# r_wiring.net
KiCad netlist of a schematic drawn in EAGLE
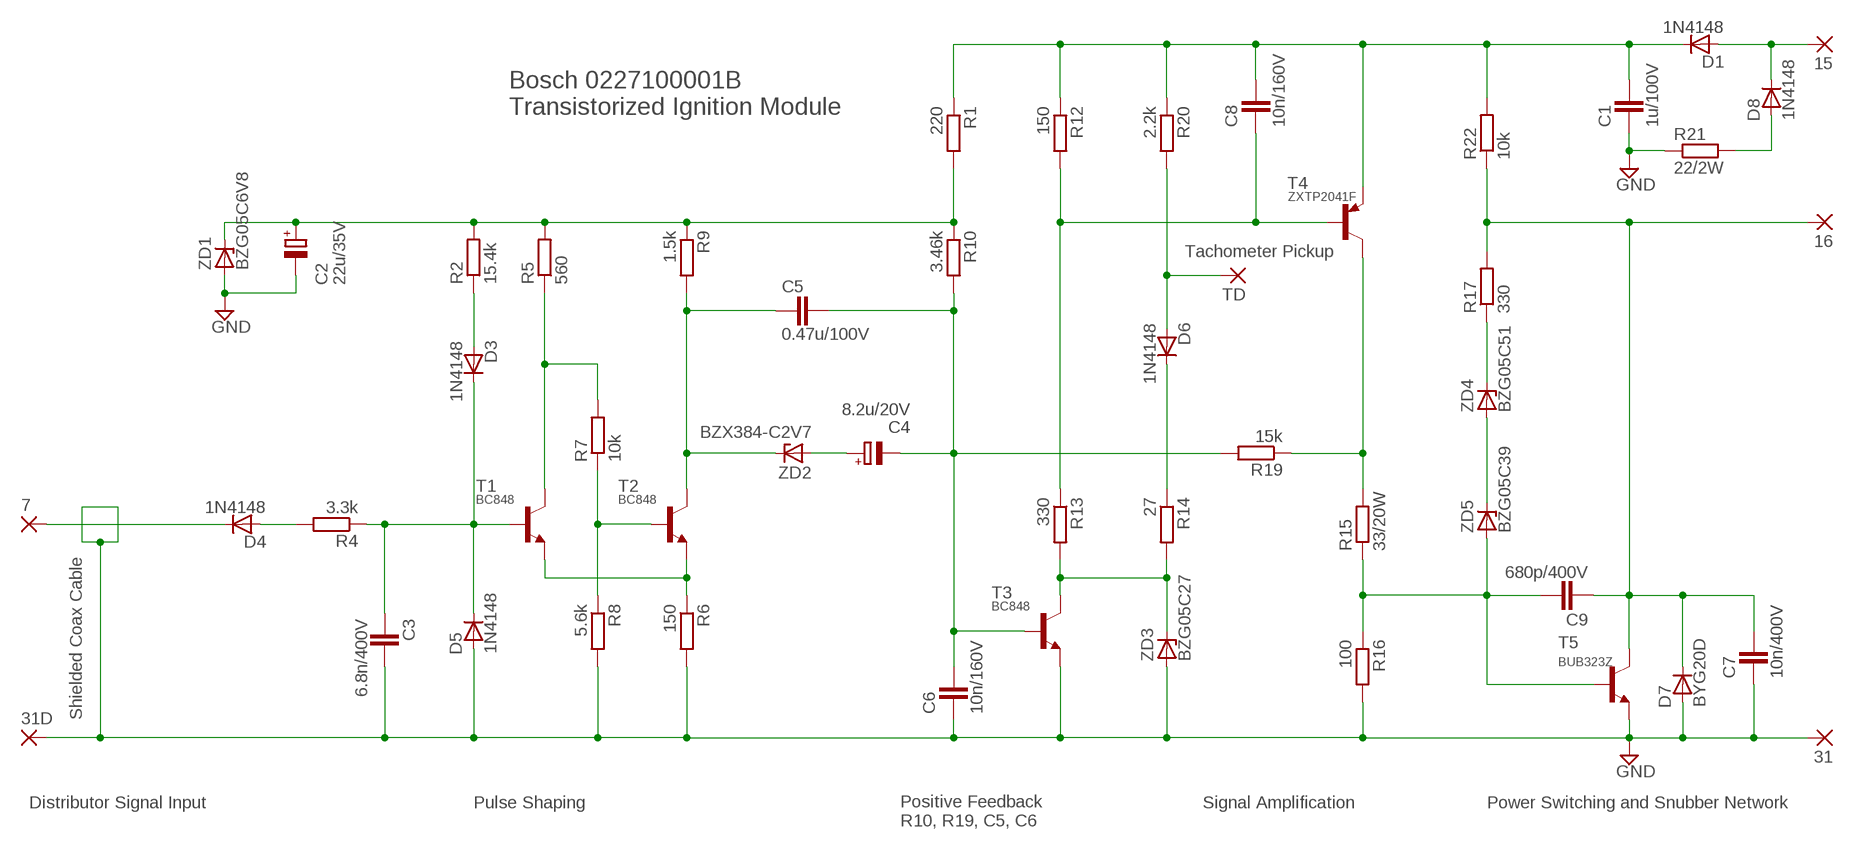
[diagram p0: schematic, sheet 1]

(export (version "E")
  (design (tool "Eeschema 10.0.6"))
  (components
    (comp (ref "7")
      (value "WIREPADSMD5-2,5")
      (footprint "eagle-import:5-2,5")
      (libsource (lib "eagle-import") (part "WIREPADSMD5-2,5"))
    )
    (comp (ref "15")
      (value "WIREPADSMD5-2,5")
      (footprint "eagle-import:5-2,5")
      (libsource (lib "eagle-import") (part "WIREPADSMD5-2,5"))
    )
    (comp (ref "16")
      (value "WIREPADSMD5-2,5")
      (footprint "eagle-import:5-2,5")
      (libsource (lib "eagle-import") (part "WIREPADSMD5-2,5"))
    )
    (comp (ref "31")
      (value "WIREPADSMD5-2,5")
      (footprint "eagle-import:5-2,5")
      (libsource (lib "eagle-import") (part "WIREPADSMD5-2,5"))
    )
    (comp (ref "31D")
      (value "WIREPADSMD5-2,5")
      (footprint "eagle-import:5-2,5")
      (libsource (lib "eagle-import") (part "WIREPADSMD5-2,5"))
    )
    (comp (ref "C1")
      (value "1u/100V")
      (footprint "eagle-import:C1206")
      (libsource (lib "eagle-import") (part "C-EUC1206"))
    )
    (comp (ref "C2")
      (value "22u/35V")
      (footprint "eagle-import:PANASONIC_G")
      (libsource (lib "eagle-import") (part "CPOL-EUG"))
    )
    (comp (ref "C3")
      (value "6.8n/400V")
      (footprint "eagle-import:C1206")
      (libsource (lib "eagle-import") (part "C-EUC1206"))
    )
    (comp (ref "C4")
      (value "8.2u/20V")
      (footprint "eagle-import:PANASONIC_G")
      (libsource (lib "eagle-import") (part "CPOL-EUG"))
    )
    (comp (ref "C5")
      (value "0.47u/100V")
      (footprint "eagle-import:C1206")
      (libsource (lib "eagle-import") (part "C-EUC1206"))
    )
    (comp (ref "C6")
      (value "10n/160V")
      (footprint "eagle-import:C1206")
      (libsource (lib "eagle-import") (part "C-EUC1206"))
    )
    (comp (ref "C7")
      (value "10n/400V")
      (footprint "eagle-import:C1206")
      (libsource (lib "eagle-import") (part "C-EUC1206"))
    )
    (comp (ref "C8")
      (value "10n/160V")
      (footprint "eagle-import:C1206")
      (libsource (lib "eagle-import") (part "C-EUC1206"))
    )
    (comp (ref "C9")
      (value "680p/400V")
      (footprint "eagle-import:C1206")
      (libsource (lib "eagle-import") (part "C-EUC1206"))
    )
    (comp (ref "D1")
      (value "1N4148")
      (footprint "eagle-import:SOD123")
      (libsource (lib "eagle-import") (part "DIODE-SOD123"))
    )
    (comp (ref "D3")
      (value "1N4148")
      (footprint "eagle-import:SOD123")
      (libsource (lib "eagle-import") (part "DIODE-SOD123"))
    )
    (comp (ref "D4")
      (value "1N4148")
      (footprint "eagle-import:SOD123")
      (libsource (lib "eagle-import") (part "DIODE-SOD123"))
    )
    (comp (ref "D5")
      (value "1N4148")
      (footprint "eagle-import:SOD123")
      (libsource (lib "eagle-import") (part "DIODE-SOD123"))
    )
    (comp (ref "D6")
      (value "1N4148")
      (footprint "eagle-import:SOD123")
      (libsource (lib "eagle-import") (part "DIODE-SOD123"))
    )
    (comp (ref "D7")
      (value "BYG20D")
      (footprint "eagle-import:DO214AC")
      (libsource (lib "eagle-import") (part "DIODE-DO214AC"))
    )
    (comp (ref "D8")
      (value "1N4148")
      (footprint "eagle-import:SOD123")
      (libsource (lib "eagle-import") (part "DIODE-SOD123"))
    )
    (comp (ref "R1")
      (value "220")
      (footprint "eagle-import:R2512")
      (libsource (lib "eagle-import") (part "resistor_R-EU_R2512"))
    )
    (comp (ref "R2")
      (value "15.4k")
      (footprint "eagle-import:R2512")
      (libsource (lib "eagle-import") (part "resistor_R-EU_R2512"))
    )
    (comp (ref "R4")
      (value "3.3k")
      (footprint "eagle-import:R2512")
      (libsource (lib "eagle-import") (part "resistor_R-EU_R2512"))
    )
    (comp (ref "R5")
      (value "560")
      (footprint "eagle-import:R2512")
      (libsource (lib "eagle-import") (part "resistor_R-EU_R2512"))
    )
    (comp (ref "R6")
      (value "150")
      (footprint "eagle-import:R2512")
      (libsource (lib "eagle-import") (part "resistor_R-EU_R2512"))
    )
    (comp (ref "R7")
      (value "10k")
      (footprint "eagle-import:R2512")
      (libsource (lib "eagle-import") (part "resistor_R-EU_R2512"))
    )
    (comp (ref "R8")
      (value "5.6k")
      (footprint "eagle-import:R2512")
      (libsource (lib "eagle-import") (part "resistor_R-EU_R2512"))
    )
    (comp (ref "R9")
      (value "1.5k")
      (footprint "eagle-import:R2512")
      (libsource (lib "eagle-import") (part "resistor_R-EU_R2512"))
    )
    (comp (ref "R10")
      (value "3.46k")
      (footprint "eagle-import:R2512")
      (libsource (lib "eagle-import") (part "resistor_R-EU_R2512"))
    )
    (comp (ref "R12")
      (value "150")
      (footprint "eagle-import:R2512")
      (libsource (lib "eagle-import") (part "resistor_R-EU_R2512"))
    )
    (comp (ref "R13")
      (value "330")
      (footprint "eagle-import:R2512")
      (libsource (lib "eagle-import") (part "resistor_R-EU_R2512"))
    )
    (comp (ref "R14")
      (value "27")
      (footprint "eagle-import:R2512")
      (libsource (lib "eagle-import") (part "resistor_R-EU_R2512"))
    )
    (comp (ref "R15")
      (value "33/20W")
      (footprint "eagle-import:DPAK")
      (libsource (lib "eagle-import") (part "R-EU_DPAK"))
    )
    (comp (ref "R16")
      (value "100")
      (footprint "eagle-import:R2512")
      (libsource (lib "eagle-import") (part "R-EU_R2512"))
    )
    (comp (ref "R17")
      (value "330")
      (footprint "eagle-import:R2512")
      (libsource (lib "eagle-import") (part "resistor_R-EU_R2512"))
    )
    (comp (ref "R19")
      (value "15k")
      (footprint "eagle-import:R2512")
      (libsource (lib "eagle-import") (part "R-EU_R2512"))
    )
    (comp (ref "R20")
      (value "2.2k")
      (footprint "eagle-import:R2512")
      (libsource (lib "eagle-import") (part "resistor_R-EU_R2512"))
    )
    (comp (ref "R21")
      (value "22/2W")
      (footprint "eagle-import:R2512")
      (libsource (lib "eagle-import") (part "resistor_R-EU_R2512"))
    )
    (comp (ref "R22")
      (value "10k")
      (footprint "eagle-import:R2512")
      (libsource (lib "eagle-import") (part "R-EU_R2512"))
    )
    (comp (ref "T1")
      (value "BC848")
      (footprint "eagle-import:SOT23")
      (libsource (lib "eagle-import") (part "BC848"))
    )
    (comp (ref "T2")
      (value "BC848")
      (footprint "eagle-import:SOT23")
      (libsource (lib "eagle-import") (part "BC848"))
    )
    (comp (ref "T3")
      (value "BC848")
      (footprint "eagle-import:SOT23")
      (libsource (lib "eagle-import") (part "BC848"))
    )
    (comp (ref "T4")
      (value "ZXTP2041F")
      (footprint "eagle-import:SOT23-BCE")
      (libsource (lib "eagle-import") (part "-PNP-SOT23-BCE"))
    )
    (comp (ref "T5")
      (value "BUB323Z")
      (footprint "eagle-import:DPAK")
      (libsource (lib "eagle-import") (part "-NPN-DPAK-BEC"))
    )
    (comp (ref "TD")
      (value "WIREPADSMD5-2,5")
      (footprint "eagle-import:5-2,5")
      (libsource (lib "eagle-import") (part "WIREPADSMD5-2,5"))
    )
    (comp (ref "ZD1")
      (value "BZG05C6V8")
      (footprint "eagle-import:SMB")
      (libsource (lib "eagle-import") (part "ZENER-DIODESMB"))
    )
    (comp (ref "ZD2")
      (value "BZX384-C2V7")
      (footprint "eagle-import:SOD-323F")
      (libsource (lib "eagle-import") (part "ZENERSOD-323F"))
    )
    (comp (ref "ZD3")
      (value "BZG05C27")
      (footprint "eagle-import:SMB")
      (libsource (lib "eagle-import") (part "ZENER-DIODESMB"))
    )
    (comp (ref "ZD4")
      (value "BZG05C51")
      (footprint "eagle-import:SMB")
      (libsource (lib "eagle-import") (part "ZENER-DIODESMB"))
    )
    (comp (ref "ZD5")
      (value "BZG05C39")
      (footprint "eagle-import:SMB")
      (libsource (lib "eagle-import") (part "ZENER-DIODESMB"))
    )
  )
  (nets
    (net (code "1") (name "GND") (class "Default")
      (node (ref "31") (pin "1") (pinfunction "P_1") (pintype "passive"))
      (node (ref "31D") (pin "1") (pinfunction "P_1") (pintype "passive"))
      (node (ref "C1") (pin "2") (pinfunction "2_2") (pintype "passive"))
      (node (ref "C2") (pin "-") (pinfunction "-_-") (pintype "passive"))
      (node (ref "C3") (pin "1") (pinfunction "1_1") (pintype "passive"))
      (node (ref "C6") (pin "2") (pinfunction "2_2") (pintype "passive"))
      (node (ref "C7") (pin "2") (pinfunction "2_2") (pintype "passive"))
      (node (ref "D5") (pin "A") (pinfunction "A_A") (pintype "passive"))
      (node (ref "D7") (pin "A") (pinfunction "A_A") (pintype "passive"))
      (node (ref "R16") (pin "2") (pinfunction "2_2") (pintype "passive"))
      (node (ref "R21") (pin "1") (pinfunction "1_1") (pintype "passive"))
      (node (ref "R6") (pin "2") (pinfunction "2_2") (pintype "passive"))
      (node (ref "R8") (pin "2") (pinfunction "2_2") (pintype "passive"))
      (node (ref "T3") (pin "2") (pinfunction "E_2") (pintype "passive"))
      (node (ref "T5") (pin "3") (pinfunction "E_3") (pintype "passive"))
      (node (ref "ZD1") (pin "A") (pinfunction "A_A") (pintype "passive"))
      (node (ref "ZD3") (pin "A") (pinfunction "A_A") (pintype "passive"))
    )
    (net (code "2") (name "Net-(7-P)") (class "Default")
      (node (ref "7") (pin "1") (pinfunction "P_1") (pintype "passive"))
      (node (ref "D4") (pin "C") (pinfunction "C_C") (pintype "passive"))
    )
    (net (code "3") (name "Net-(15-P)") (class "Default")
      (node (ref "15") (pin "1") (pinfunction "P_1") (pintype "passive"))
      (node (ref "D1") (pin "A") (pinfunction "A_A") (pintype "passive"))
      (node (ref "D8") (pin "C") (pinfunction "C_C") (pintype "passive"))
    )
    (net (code "4") (name "Net-(16-P)") (class "Default")
      (node (ref "16") (pin "1") (pinfunction "P_1") (pintype "passive"))
      (node (ref "C7") (pin "1") (pinfunction "1_1") (pintype "passive"))
      (node (ref "C9") (pin "2") (pinfunction "2_2") (pintype "passive"))
      (node (ref "D7") (pin "C") (pinfunction "C_C") (pintype "passive"))
      (node (ref "R17") (pin "2") (pinfunction "2_2") (pintype "passive"))
      (node (ref "R22") (pin "1") (pinfunction "1_1") (pintype "passive"))
      (node (ref "T5") (pin "4") (pinfunction "C_4") (pintype "passive"))
    )
    (net (code "5") (name "Net-(C1-Pad1)") (class "Default")
      (node (ref "C1") (pin "1") (pinfunction "1_1") (pintype "passive"))
      (node (ref "C8") (pin "1") (pinfunction "1_1") (pintype "passive"))
      (node (ref "D1") (pin "C") (pinfunction "C_C") (pintype "passive"))
      (node (ref "R1") (pin "1") (pinfunction "1_1") (pintype "passive"))
      (node (ref "R12") (pin "1") (pinfunction "1_1") (pintype "passive"))
      (node (ref "R20") (pin "1") (pinfunction "1_1") (pintype "passive"))
      (node (ref "R22") (pin "2") (pinfunction "2_2") (pintype "passive"))
      (node (ref "T4") (pin "E") (pinfunction "E_E") (pintype "passive"))
    )
    (net (code "6") (name "Net-(C2-Pad+)") (class "Default")
      (node (ref "C2") (pin "+") (pinfunction "+_+") (pintype "passive"))
      (node (ref "R1") (pin "2") (pinfunction "2_2") (pintype "passive"))
      (node (ref "R10") (pin "1") (pinfunction "1_1") (pintype "passive"))
      (node (ref "R2") (pin "2") (pinfunction "2_2") (pintype "passive"))
      (node (ref "R5") (pin "2") (pinfunction "2_2") (pintype "passive"))
      (node (ref "R9") (pin "1") (pinfunction "1_1") (pintype "passive"))
      (node (ref "ZD1") (pin "C") (pinfunction "C_C") (pintype "passive"))
    )
    (net (code "7") (name "Net-(C4-Pad+)") (class "Default")
      (node (ref "C4") (pin "+") (pinfunction "+_+") (pintype "passive"))
      (node (ref "ZD2") (pin "A") (pinfunction "A_A") (pintype "passive"))
    )
    (net (code "8") (name "Net-(C8-Pad2)") (class "Default")
      (node (ref "C8") (pin "2") (pinfunction "2_2") (pintype "passive"))
      (node (ref "R12") (pin "2") (pinfunction "2_2") (pintype "passive"))
      (node (ref "R13") (pin "1") (pinfunction "1_1") (pintype "passive"))
      (node (ref "T4") (pin "B") (pinfunction "B_B") (pintype "passive"))
    )
    (net (code "9") (name "Net-(D3-PadA)") (class "Default")
      (node (ref "D3") (pin "A") (pinfunction "A_A") (pintype "passive"))
      (node (ref "R2") (pin "1") (pinfunction "1_1") (pintype "passive"))
    )
    (net (code "10") (name "Net-(D4-PadA)") (class "Default")
      (node (ref "D4") (pin "A") (pinfunction "A_A") (pintype "passive"))
      (node (ref "R4") (pin "2") (pinfunction "2_2") (pintype "passive"))
    )
    (net (code "11") (name "Net-(D6-PadC)") (class "Default")
      (node (ref "D6") (pin "C") (pinfunction "C_C") (pintype "passive"))
      (node (ref "R14") (pin "1") (pinfunction "1_1") (pintype "passive"))
    )
    (net (code "12") (name "Net-(D8-PadA)") (class "Default")
      (node (ref "D8") (pin "A") (pinfunction "A_A") (pintype "passive"))
      (node (ref "R21") (pin "2") (pinfunction "2_2") (pintype "passive"))
    )
    (net (code "13") (name "Net-(R15-2)") (class "Default")
      (node (ref "R15") (pin "3") (pinfunction "2_3") (pintype "passive"))
      (node (ref "R19") (pin "1") (pinfunction "1_1") (pintype "passive"))
      (node (ref "T4") (pin "C") (pinfunction "C_C") (pintype "passive"))
    )
    (net (code "14") (name "Net-(R17-Pad1)") (class "Default")
      (node (ref "R17") (pin "1") (pinfunction "1_1") (pintype "passive"))
      (node (ref "ZD4") (pin "C") (pinfunction "C_C") (pintype "passive"))
    )
    (net (code "15") (name "Net-(T1-B)") (class "Default")
      (node (ref "C3") (pin "2") (pinfunction "2_2") (pintype "passive"))
      (node (ref "D3") (pin "C") (pinfunction "C_C") (pintype "passive"))
      (node (ref "D5") (pin "C") (pinfunction "C_C") (pintype "passive"))
      (node (ref "R4") (pin "1") (pinfunction "1_1") (pintype "passive"))
      (node (ref "T1") (pin "1") (pinfunction "B_1") (pintype "passive"))
    )
    (net (code "16") (name "Net-(T1-C)") (class "Default")
      (node (ref "R5") (pin "1") (pinfunction "1_1") (pintype "passive"))
      (node (ref "R7") (pin "2") (pinfunction "2_2") (pintype "passive"))
      (node (ref "T1") (pin "3") (pinfunction "C_3") (pintype "passive"))
    )
    (net (code "17") (name "Net-(T1-E)") (class "Default")
      (node (ref "R6") (pin "1") (pinfunction "1_1") (pintype "passive"))
      (node (ref "T1") (pin "2") (pinfunction "E_2") (pintype "passive"))
      (node (ref "T2") (pin "2") (pinfunction "E_2") (pintype "passive"))
    )
    (net (code "18") (name "Net-(T2-B)") (class "Default")
      (node (ref "R7") (pin "1") (pinfunction "1_1") (pintype "passive"))
      (node (ref "R8") (pin "1") (pinfunction "1_1") (pintype "passive"))
      (node (ref "T2") (pin "1") (pinfunction "B_1") (pintype "passive"))
    )
    (net (code "19") (name "Net-(T2-C)") (class "Default")
      (node (ref "C5") (pin "2") (pinfunction "2_2") (pintype "passive"))
      (node (ref "R9") (pin "2") (pinfunction "2_2") (pintype "passive"))
      (node (ref "T2") (pin "3") (pinfunction "C_3") (pintype "passive"))
      (node (ref "ZD2") (pin "C") (pinfunction "C_C") (pintype "passive"))
    )
    (net (code "20") (name "Net-(T3-B)") (class "Default")
      (node (ref "C4") (pin "-") (pinfunction "-_-") (pintype "passive"))
      (node (ref "C5") (pin "1") (pinfunction "1_1") (pintype "passive"))
      (node (ref "C6") (pin "1") (pinfunction "1_1") (pintype "passive"))
      (node (ref "R10") (pin "2") (pinfunction "2_2") (pintype "passive"))
      (node (ref "R19") (pin "2") (pinfunction "2_2") (pintype "passive"))
      (node (ref "T3") (pin "1") (pinfunction "B_1") (pintype "passive"))
    )
    (net (code "21") (name "Net-(T3-C)") (class "Default")
      (node (ref "R13") (pin "2") (pinfunction "2_2") (pintype "passive"))
      (node (ref "R14") (pin "2") (pinfunction "2_2") (pintype "passive"))
      (node (ref "T3") (pin "3") (pinfunction "C_3") (pintype "passive"))
      (node (ref "ZD3") (pin "C") (pinfunction "C_C") (pintype "passive"))
    )
    (net (code "22") (name "Net-(T5-B)") (class "Default")
      (node (ref "C9") (pin "1") (pinfunction "1_1") (pintype "passive"))
      (node (ref "R15") (pin "1") (pinfunction "1_1") (pintype "passive"))
      (node (ref "R16") (pin "1") (pinfunction "1_1") (pintype "passive"))
      (node (ref "T5") (pin "1") (pinfunction "B_1") (pintype "passive"))
      (node (ref "ZD5") (pin "A") (pinfunction "A_A") (pintype "passive"))
    )
    (net (code "23") (name "Net-(TD-P)") (class "Default")
      (node (ref "D6") (pin "A") (pinfunction "A_A") (pintype "passive"))
      (node (ref "R20") (pin "2") (pinfunction "2_2") (pintype "passive"))
      (node (ref "TD") (pin "1") (pinfunction "P_1") (pintype "passive"))
    )
    (net (code "24") (name "Net-(ZD4-PadA)") (class "Default")
      (node (ref "ZD4") (pin "A") (pinfunction "A_A") (pintype "passive"))
      (node (ref "ZD5") (pin "C") (pinfunction "C_C") (pintype "passive"))
    )
  )
)
